# ADC_final.net
KiCad netlist of a schematic drawn in EAGLE
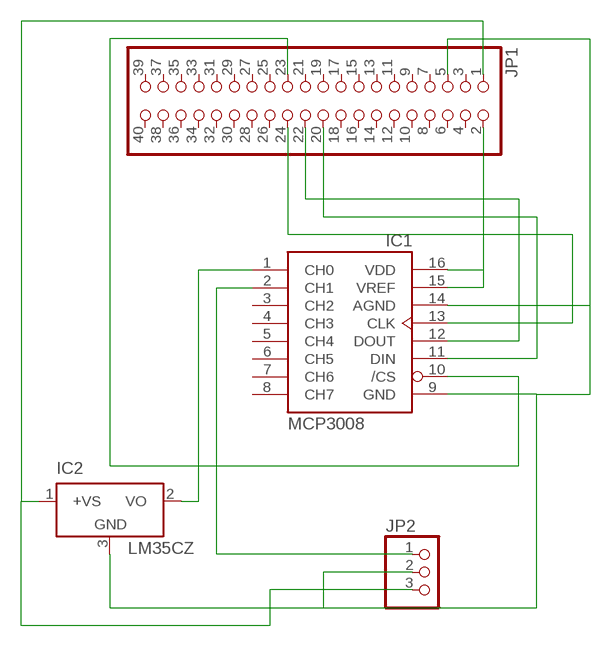
[diagram p0: schematic, sheet 1]

(export (version "E")
  (design (tool "Eeschema 10.0.6"))
  (components
    (comp (ref "IC1")
      (value "MCP3008")
      (footprint "eagle-import:DIL16")
      (libsource (lib "eagle-import") (part "MCP3008"))
    )
    (comp (ref "IC2")
      (value "LM35CZ")
      (footprint "eagle-import:TO92")
      (libsource (lib "eagle-import") (part "LM35CZ"))
    )
    (comp (ref "JP1")
      (value "PINHD-2X20")
      (footprint "eagle-import:2X20")
      (libsource (lib "eagle-import") (part "PINHD-2X20"))
    )
    (comp (ref "JP2")
      (value "PINHD-1X3M")
      (footprint "eagle-import:1X03M")
      (libsource (lib "eagle-import") (part "PINHD-1X3M"))
    )
  )
  (nets
    (net (code "1") (name "Net-(IC1-AGND)") (class "Default")
      (node (ref "IC1") (pin "14") (pinfunction "AGND_14") (pintype "power_in"))
      (node (ref "IC1") (pin "9") (pinfunction "GND_9") (pintype "power_in"))
      (node (ref "IC2") (pin "3") (pinfunction "GND_3") (pintype "power_in"))
      (node (ref "JP1") (pin "5") (pinfunction "5_5") (pintype "passive"))
      (node (ref "JP2") (pin "2") (pinfunction "2_2") (pintype "passive"))
    )
    (net (code "2") (name "Net-(IC1-CH0)") (class "Default")
      (node (ref "IC1") (pin "1") (pinfunction "CH0_1") (pintype "input"))
      (node (ref "IC2") (pin "2") (pinfunction "VO_2") (pintype "input"))
    )
    (net (code "3") (name "Net-(IC1-CH1)") (class "Default")
      (node (ref "IC1") (pin "2") (pinfunction "CH1_2") (pintype "input"))
      (node (ref "JP2") (pin "1") (pinfunction "1_1") (pintype "passive"))
    )
    (net (code "4") (name "Net-(IC1-CLK)") (class "Default")
      (node (ref "IC1") (pin "13") (pinfunction "CLK_13") (pintype "input"))
      (node (ref "JP1") (pin "24") (pinfunction "24_24") (pintype "passive"))
    )
    (net (code "5") (name "Net-(IC1-DIN)") (class "Default")
      (node (ref "IC1") (pin "11") (pinfunction "DIN_11") (pintype "input"))
      (node (ref "JP1") (pin "20") (pinfunction "20_20") (pintype "passive"))
    )
    (net (code "6") (name "Net-(IC1-DOUT)") (class "Default")
      (node (ref "IC1") (pin "12") (pinfunction "DOUT_12") (pintype "output"))
      (node (ref "JP1") (pin "22") (pinfunction "22_22") (pintype "passive"))
    )
    (net (code "7") (name "Net-(IC1-VDD)") (class "Default")
      (node (ref "IC1") (pin "15") (pinfunction "VREF_15") (pintype "input"))
      (node (ref "IC1") (pin "16") (pinfunction "VDD_16") (pintype "power_in"))
      (node (ref "JP1") (pin "2") (pinfunction "2_2") (pintype "passive"))
    )
    (net (code "8") (name "Net-(IC1-{slash}CS)") (class "Default")
      (node (ref "IC1") (pin "10") (pinfunction "/CS_10") (pintype "input"))
      (node (ref "JP1") (pin "23") (pinfunction "23_23") (pintype "passive"))
    )
    (net (code "9") (name "Net-(IC2-+VS)") (class "Default")
      (node (ref "IC2") (pin "1") (pinfunction "+VS_1") (pintype "input"))
      (node (ref "JP1") (pin "1") (pinfunction "1_1") (pintype "passive"))
      (node (ref "JP2") (pin "3") (pinfunction "3_3") (pintype "passive"))
    )
    (net (code "10") (name "unconnected-(IC1-CH2-Pad3)") (class "Default")
      (node (ref "IC1") (pin "3") (pinfunction "CH2_3") (pintype "input"))
    )
    (net (code "11") (name "unconnected-(IC1-CH3-Pad4)") (class "Default")
      (node (ref "IC1") (pin "4") (pinfunction "CH3_4") (pintype "input"))
    )
    (net (code "12") (name "unconnected-(IC1-CH4-Pad5)") (class "Default")
      (node (ref "IC1") (pin "5") (pinfunction "CH4_5") (pintype "input"))
    )
    (net (code "13") (name "unconnected-(IC1-CH5-Pad6)") (class "Default")
      (node (ref "IC1") (pin "6") (pinfunction "CH5_6") (pintype "input"))
    )
    (net (code "14") (name "unconnected-(IC1-CH6-Pad7)") (class "Default")
      (node (ref "IC1") (pin "7") (pinfunction "CH6_7") (pintype "input"))
    )
    (net (code "15") (name "unconnected-(IC1-CH7-Pad8)") (class "Default")
      (node (ref "IC1") (pin "8") (pinfunction "CH7_8") (pintype "input"))
    )
    (net (code "16") (name "unconnected-(JP1-Pad3)") (class "Default")
      (node (ref "JP1") (pin "3") (pinfunction "3_3") (pintype "passive"))
    )
    (net (code "17") (name "unconnected-(JP1-Pad4)") (class "Default")
      (node (ref "JP1") (pin "4") (pinfunction "4_4") (pintype "passive"))
    )
    (net (code "18") (name "unconnected-(JP1-Pad6)") (class "Default")
      (node (ref "JP1") (pin "6") (pinfunction "6_6") (pintype "passive"))
    )
    (net (code "19") (name "unconnected-(JP1-Pad7)") (class "Default")
      (node (ref "JP1") (pin "7") (pinfunction "7_7") (pintype "passive"))
    )
    (net (code "20") (name "unconnected-(JP1-Pad8)") (class "Default")
      (node (ref "JP1") (pin "8") (pinfunction "8_8") (pintype "passive"))
    )
    (net (code "21") (name "unconnected-(JP1-Pad9)") (class "Default")
      (node (ref "JP1") (pin "9") (pinfunction "9_9") (pintype "passive"))
    )
    (net (code "22") (name "unconnected-(JP1-Pad10)") (class "Default")
      (node (ref "JP1") (pin "10") (pinfunction "10_10") (pintype "passive"))
    )
    (net (code "23") (name "unconnected-(JP1-Pad11)") (class "Default")
      (node (ref "JP1") (pin "11") (pinfunction "11_11") (pintype "passive"))
    )
    (net (code "24") (name "unconnected-(JP1-Pad12)") (class "Default")
      (node (ref "JP1") (pin "12") (pinfunction "12_12") (pintype "passive"))
    )
    (net (code "25") (name "unconnected-(JP1-Pad13)") (class "Default")
      (node (ref "JP1") (pin "13") (pinfunction "13_13") (pintype "passive"))
    )
    (net (code "26") (name "unconnected-(JP1-Pad14)") (class "Default")
      (node (ref "JP1") (pin "14") (pinfunction "14_14") (pintype "passive"))
    )
    (net (code "27") (name "unconnected-(JP1-Pad15)") (class "Default")
      (node (ref "JP1") (pin "15") (pinfunction "15_15") (pintype "passive"))
    )
    (net (code "28") (name "unconnected-(JP1-Pad16)") (class "Default")
      (node (ref "JP1") (pin "16") (pinfunction "16_16") (pintype "passive"))
    )
    (net (code "29") (name "unconnected-(JP1-Pad17)") (class "Default")
      (node (ref "JP1") (pin "17") (pinfunction "17_17") (pintype "passive"))
    )
    (net (code "30") (name "unconnected-(JP1-Pad18)") (class "Default")
      (node (ref "JP1") (pin "18") (pinfunction "18_18") (pintype "passive"))
    )
    (net (code "31") (name "unconnected-(JP1-Pad19)") (class "Default")
      (node (ref "JP1") (pin "19") (pinfunction "19_19") (pintype "passive"))
    )
    (net (code "32") (name "unconnected-(JP1-Pad21)") (class "Default")
      (node (ref "JP1") (pin "21") (pinfunction "21_21") (pintype "passive"))
    )
    (net (code "33") (name "unconnected-(JP1-Pad25)") (class "Default")
      (node (ref "JP1") (pin "25") (pinfunction "25_25") (pintype "passive"))
    )
    (net (code "34") (name "unconnected-(JP1-Pad26)") (class "Default")
      (node (ref "JP1") (pin "26") (pinfunction "26_26") (pintype "passive"))
    )
    (net (code "35") (name "unconnected-(JP1-Pad27)") (class "Default")
      (node (ref "JP1") (pin "27") (pinfunction "27_27") (pintype "passive"))
    )
    (net (code "36") (name "unconnected-(JP1-Pad28)") (class "Default")
      (node (ref "JP1") (pin "28") (pinfunction "28_28") (pintype "passive"))
    )
    (net (code "37") (name "unconnected-(JP1-Pad29)") (class "Default")
      (node (ref "JP1") (pin "29") (pinfunction "29_29") (pintype "passive"))
    )
    (net (code "38") (name "unconnected-(JP1-Pad30)") (class "Default")
      (node (ref "JP1") (pin "30") (pinfunction "30_30") (pintype "passive"))
    )
    (net (code "39") (name "unconnected-(JP1-Pad31)") (class "Default")
      (node (ref "JP1") (pin "31") (pinfunction "31_31") (pintype "passive"))
    )
    (net (code "40") (name "unconnected-(JP1-Pad32)") (class "Default")
      (node (ref "JP1") (pin "32") (pinfunction "32_32") (pintype "passive"))
    )
    (net (code "41") (name "unconnected-(JP1-Pad33)") (class "Default")
      (node (ref "JP1") (pin "33") (pinfunction "33_33") (pintype "passive"))
    )
    (net (code "42") (name "unconnected-(JP1-Pad34)") (class "Default")
      (node (ref "JP1") (pin "34") (pinfunction "34_34") (pintype "passive"))
    )
    (net (code "43") (name "unconnected-(JP1-Pad35)") (class "Default")
      (node (ref "JP1") (pin "35") (pinfunction "35_35") (pintype "passive"))
    )
    (net (code "44") (name "unconnected-(JP1-Pad36)") (class "Default")
      (node (ref "JP1") (pin "36") (pinfunction "36_36") (pintype "passive"))
    )
    (net (code "45") (name "unconnected-(JP1-Pad37)") (class "Default")
      (node (ref "JP1") (pin "37") (pinfunction "37_37") (pintype "passive"))
    )
    (net (code "46") (name "unconnected-(JP1-Pad38)") (class "Default")
      (node (ref "JP1") (pin "38") (pinfunction "38_38") (pintype "passive"))
    )
    (net (code "47") (name "unconnected-(JP1-Pad39)") (class "Default")
      (node (ref "JP1") (pin "39") (pinfunction "39_39") (pintype "passive"))
    )
    (net (code "48") (name "unconnected-(JP1-Pad40)") (class "Default")
      (node (ref "JP1") (pin "40") (pinfunction "40_40") (pintype "passive"))
    )
  )
)
